# 1_SchDoc.net
KiCad netlist of a schematic drawn in Altium Designer
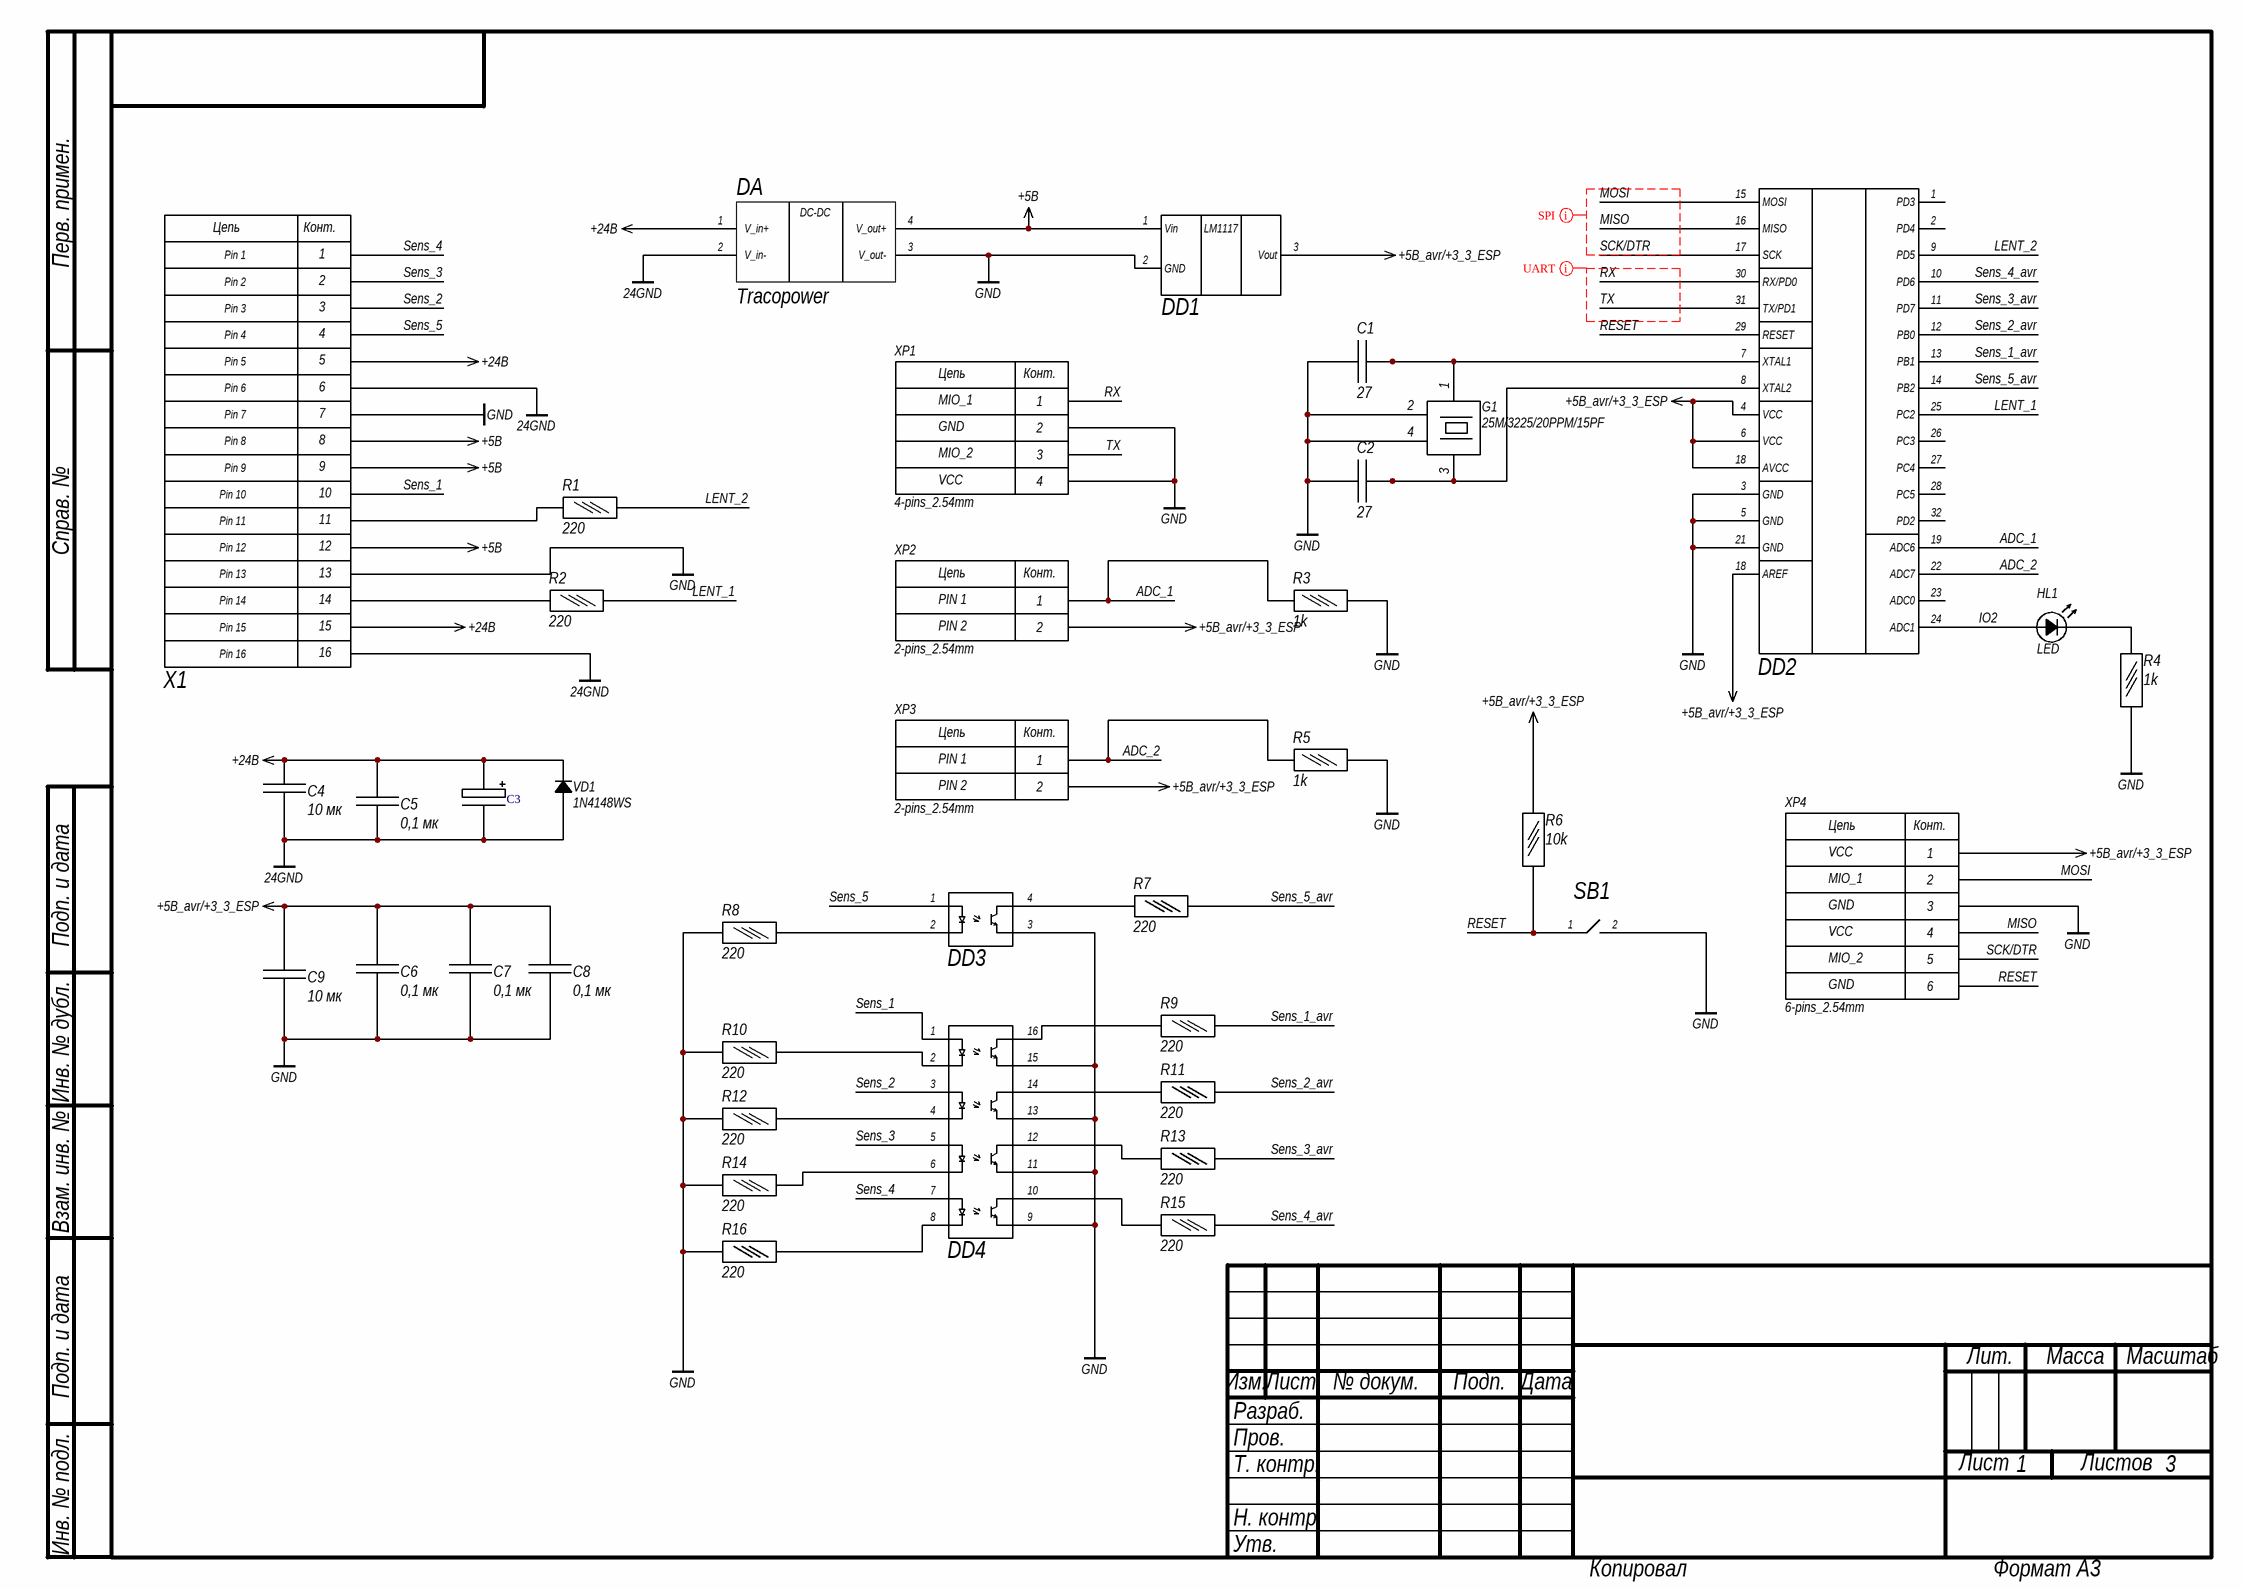
[diagram p0: Лист 1. Основной модуль. SchDoc.SchDoc]

(export (version "E")
  (design (tool "Eeschema 10.0.6"))
  (components
    (comp (ref "C1")
      (value "27")
      (footprint "CAPC1608M")
      (description "0603 X7R 0,1uF 25V 10%")
      (fields
        (field (name "VALUEMANUFACTURERPARTNUMBER") "chip0603 X7R 0,1uF 50V 10%, CC0603KRX7R9BB104, Yageo")
        (field (name "Comment") "CC0603KRX7R8BB104 (0603 X7R 0,1uF 50V 10%)_1")
      )
      (libsource (lib "Конденсаторы") (part "CC0603KRX7R8BB104 (0603 X7R 0,1uF 50V 10%)_1"))
    )
    (comp (ref "C2")
      (value "27")
      (footprint "CAPC1608M")
      (description "0603 X7R 0,1uF 25V 10%")
      (fields
        (field (name "VALUEMANUFACTURERPARTNUMBER") "chip0603 X7R 0,1uF 50V 10%, CC0603KRX7R9BB104, Yageo")
        (field (name "Comment") "CC0603KRX7R8BB104 (0603 X7R 0,1uF 50V 10%)_1")
      )
      (libsource (lib "Конденсаторы") (part "CC0603KRX7R8BB104 (0603 X7R 0,1uF 50V 10%)_1"))
    )
    (comp (ref "C3")
      (value "CAP_SMD_POLAR")
      (footprint "CC_T491C476K016AT")
      (libsource (lib "Cap") (part "CAP_SMD_POLAR"))
    )
    (comp (ref "C4")
      (value "10 мк")
      (footprint "CAPC1608M")
      (description "0603 X7R 0,1uF 25V 10%")
      (fields
        (field (name "VALUEMANUFACTURERPARTNUMBER") "chip0603 X7R 0,1uF 50V 10%, CC0603KRX7R9BB104, Yageo")
        (field (name "Comment") "CC0603KRX7R8BB104 (0603 X7R 0,1uF 50V 10%)_1")
      )
      (libsource (lib "Конденсаторы") (part "CC0603KRX7R8BB104 (0603 X7R 0,1uF 50V 10%)_1"))
    )
    (comp (ref "C5")
      (value "0,1 мк")
      (footprint "CAPC1608M")
      (description "0603 X7R 0,1uF 25V 10%")
      (fields
        (field (name "VALUEMANUFACTURERPARTNUMBER") "chip0603 X7R 0,1uF 50V 10%, CC0603KRX7R9BB104, Yageo")
        (field (name "Comment") "CC0603KRX7R8BB104 (0603 X7R 0,1uF 50V 10%)_1")
      )
      (libsource (lib "Конденсаторы") (part "CC0603KRX7R8BB104 (0603 X7R 0,1uF 50V 10%)_1"))
    )
    (comp (ref "C6")
      (value "0,1 мк")
      (footprint "CAPC1608M")
      (description "0603 X7R 0,1uF 25V 10%")
      (fields
        (field (name "VALUEMANUFACTURERPARTNUMBER") "chip0603 X7R 0,1uF 50V 10%, CC0603KRX7R9BB104, Yageo")
        (field (name "Comment") "CC0603KRX7R8BB104 (0603 X7R 0,1uF 50V 10%)_1")
      )
      (libsource (lib "Конденсаторы") (part "CC0603KRX7R8BB104 (0603 X7R 0,1uF 50V 10%)_1"))
    )
    (comp (ref "C7")
      (value "0,1 мк")
      (footprint "CAPC1608M")
      (description "0603 X7R 0,1uF 25V 10%")
      (fields
        (field (name "VALUEMANUFACTURERPARTNUMBER") "chip0603 X7R 0,1uF 50V 10%, CC0603KRX7R9BB104, Yageo")
        (field (name "Comment") "CC0603KRX7R8BB104 (0603 X7R 0,1uF 50V 10%)_1")
      )
      (libsource (lib "Конденсаторы") (part "CC0603KRX7R8BB104 (0603 X7R 0,1uF 50V 10%)_1"))
    )
    (comp (ref "C8")
      (value "0,1 мк")
      (footprint "CAPC1608M")
      (description "0603 X7R 0,1uF 25V 10%")
      (fields
        (field (name "VALUEMANUFACTURERPARTNUMBER") "chip0603 X7R 0,1uF 50V 10%, CC0603KRX7R9BB104, Yageo")
        (field (name "Comment") "CC0603KRX7R8BB104 (0603 X7R 0,1uF 50V 10%)_1")
      )
      (libsource (lib "Конденсаторы") (part "CC0603KRX7R8BB104 (0603 X7R 0,1uF 50V 10%)_1"))
    )
    (comp (ref "C9")
      (value "10 мк")
      (footprint "CAPC1608M")
      (description "0603 X7R 0,1uF 25V 10%")
      (fields
        (field (name "VALUEMANUFACTURERPARTNUMBER") "chip0603 X7R 0,1uF 50V 10%, CC0603KRX7R9BB104, Yageo")
        (field (name "Comment") "CC0603KRX7R8BB104 (0603 X7R 0,1uF 50V 10%)_1")
      )
      (libsource (lib "Конденсаторы") (part "CC0603KRX7R8BB104 (0603 X7R 0,1uF 50V 10%)_1"))
    )
    (comp (ref "DA")
      (value "Tracopower")
      (footprint "Tracopower")
      (libsource (lib "Microsxeme") (part "TracoPower"))
    )
    (comp (ref "DD1") (value "LM1117") (footprint "SOT-223") (libsource (lib "DC-DC") (part "LM1117")))
    (comp (ref "DD2")
      (value "ATmega328p")
      (footprint "ATmega328P_TQFP")
      (description "32 pins. SPI, UART, 4 CHANNELS ADC, 13 GPIO PORTS")
      (libsource (lib "AVR") (part "ATmega328p"))
    )
    (comp (ref "DD3") (value "IS-281") (footprint "IS-281") (libsource (lib "Opto") (part "IS-281")))
    (comp (ref "DD4") (value "IS-281-4") (footprint "SOIC16") (libsource (lib "Opto") (part "IS-281-4")))
    (comp (ref "G1")
      (value "25M/3225/20PPM/15PF")
      (footprint "EPSON TSX-3225")
      (description "7B025000O01 Резонатор")
      (fields (field (name "VALUEMANUFACTURERPARTNUMBER") "7B25000O01"))
      (libsource (lib "микросхемы") (part "25M/3225/20PPM/15PF"))
    )
    (comp (ref "HL1")
      (value "LED")
      (footprint "LED 0603_1608 BLUE")
      (description "Chip LED")
      (fields (field (name "VALUEMANUFACTURERPARTNUMBER") "Светодиод"))
      (libsource (lib "микросхемы") (part "LED"))
    )
    (comp (ref "R1")
      (value "220")
      (footprint "RESC1608M")
      (description "chip0603 10k 1%")
      (fields
        (field (name "VALUEMANUFACTURERPARTNUMBER") "chip0603 10k 1%, RC0603FR-0710KL, Yageo")
        (field (name "Comment") "RC0603FR-0710KL (0603 10k 1%)")
      )
      (libsource (lib "Резисторы") (part "RC0603FR-0710KL (0603 10k 1%)"))
    )
    (comp (ref "R2")
      (value "220")
      (footprint "RESC1608M")
      (description "chip0603 10k 1%")
      (fields
        (field (name "VALUEMANUFACTURERPARTNUMBER") "chip0603 10k 1%, RC0603FR-0710KL, Yageo")
        (field (name "Comment") "RC0603FR-0710KL (0603 10k 1%)")
      )
      (libsource (lib "Резисторы") (part "RC0603FR-0710KL (0603 10k 1%)"))
    )
    (comp (ref "R3")
      (value "1k")
      (footprint "RESC1608M")
      (description "chip0603 1k 1%")
      (fields
        (field (name "VALUEMANUFACTURERPARTNUMBER") "chip0603 1k 1%, RC0603FR-071KL, Yageo")
        (field (name "Comment") "RC0603FR-071KL (0603 1k 1%)")
      )
      (libsource (lib "Резисторы") (part "RC0603FR-071KL (0603 1k 1%)"))
    )
    (comp (ref "R4")
      (value "1k")
      (footprint "RESC1608M")
      (description "chip0603 1k 1%")
      (fields
        (field (name "VALUEMANUFACTURERPARTNUMBER") "chip0603 1k 1%, RC0603FR-071KL, Yageo")
        (field (name "Comment") "RC0603FR-071KL (0603 1k 1%)")
      )
      (libsource (lib "Резисторы") (part "RC0603FR-071KL (0603 1k 1%)"))
    )
    (comp (ref "R5")
      (value "1k")
      (footprint "RESC1608M")
      (description "chip0603 1k 1%")
      (fields
        (field (name "VALUEMANUFACTURERPARTNUMBER") "chip0603 1k 1%, RC0603FR-071KL, Yageo")
        (field (name "Comment") "RC0603FR-071KL (0603 1k 1%)")
      )
      (libsource (lib "Резисторы") (part "RC0603FR-071KL (0603 1k 1%)"))
    )
    (comp (ref "R6")
      (value "10k")
      (footprint "RESC1608M")
      (description "chip0603 10k 1%")
      (fields
        (field (name "VALUEMANUFACTURERPARTNUMBER") "chip0603 10k 1%, RC0603FR-0710KL, Yageo")
        (field (name "Comment") "RC0603FR-0710KL (0603 10k 1%)")
      )
      (libsource (lib "Резисторы") (part "RC0603FR-0710KL (0603 10k 1%)"))
    )
    (comp (ref "R7")
      (value "220")
      (footprint "RESC1608M")
      (description "chip0603 10k 1%")
      (fields
        (field (name "VALUEMANUFACTURERPARTNUMBER") "chip0603 10k 1%, RC0603FR-0710KL, Yageo")
        (field (name "Comment") "RC0603FR-0710KL (0603 10k 1%)")
      )
      (libsource (lib "Резисторы") (part "RC0603FR-0710KL (0603 10k 1%)"))
    )
    (comp (ref "R8")
      (value "220")
      (footprint "RESC1608M")
      (description "chip0603 10k 1%")
      (fields
        (field (name "VALUEMANUFACTURERPARTNUMBER") "chip0603 10k 1%, RC0603FR-0710KL, Yageo")
        (field (name "Comment") "RC0603FR-0710KL (0603 10k 1%)")
      )
      (libsource (lib "Резисторы") (part "RC0603FR-0710KL (0603 10k 1%)"))
    )
    (comp (ref "R9")
      (value "220")
      (footprint "RESC1608M")
      (description "chip0603 10k 1%")
      (fields
        (field (name "VALUEMANUFACTURERPARTNUMBER") "chip0603 10k 1%, RC0603FR-0710KL, Yageo")
        (field (name "Comment") "RC0603FR-0710KL (0603 10k 1%)")
      )
      (libsource (lib "Резисторы") (part "RC0603FR-0710KL (0603 10k 1%)"))
    )
    (comp (ref "R10")
      (value "220")
      (footprint "RESC1608M")
      (description "chip0603 10k 1%")
      (fields
        (field (name "VALUEMANUFACTURERPARTNUMBER") "chip0603 10k 1%, RC0603FR-0710KL, Yageo")
        (field (name "Comment") "RC0603FR-0710KL (0603 10k 1%)")
      )
      (libsource (lib "Резисторы") (part "RC0603FR-0710KL (0603 10k 1%)"))
    )
    (comp (ref "R11")
      (value "220")
      (footprint "RESC1608M")
      (description "chip0603 10k 1%")
      (fields
        (field (name "VALUEMANUFACTURERPARTNUMBER") "chip0603 10k 1%, RC0603FR-0710KL, Yageo")
        (field (name "Comment") "RC0603FR-0710KL (0603 10k 1%)")
      )
      (libsource (lib "Резисторы") (part "RC0603FR-0710KL (0603 10k 1%)"))
    )
    (comp (ref "R12")
      (value "220")
      (footprint "RESC1608M")
      (description "chip0603 10k 1%")
      (fields
        (field (name "VALUEMANUFACTURERPARTNUMBER") "chip0603 10k 1%, RC0603FR-0710KL, Yageo")
        (field (name "Comment") "RC0603FR-0710KL (0603 10k 1%)")
      )
      (libsource (lib "Резисторы") (part "RC0603FR-0710KL (0603 10k 1%)"))
    )
    (comp (ref "R13")
      (value "220")
      (footprint "RESC1608M")
      (description "chip0603 10k 1%")
      (fields
        (field (name "VALUEMANUFACTURERPARTNUMBER") "chip0603 10k 1%, RC0603FR-0710KL, Yageo")
        (field (name "Comment") "RC0603FR-0710KL (0603 10k 1%)")
      )
      (libsource (lib "Резисторы") (part "RC0603FR-0710KL (0603 10k 1%)"))
    )
    (comp (ref "R14")
      (value "220")
      (footprint "RESC1608M")
      (description "chip0603 10k 1%")
      (fields
        (field (name "VALUEMANUFACTURERPARTNUMBER") "chip0603 10k 1%, RC0603FR-0710KL, Yageo")
        (field (name "Comment") "RC0603FR-0710KL (0603 10k 1%)")
      )
      (libsource (lib "Резисторы") (part "RC0603FR-0710KL (0603 10k 1%)"))
    )
    (comp (ref "R15")
      (value "220")
      (footprint "RESC1608M")
      (description "chip0603 10k 1%")
      (fields
        (field (name "VALUEMANUFACTURERPARTNUMBER") "chip0603 10k 1%, RC0603FR-0710KL, Yageo")
        (field (name "Comment") "RC0603FR-0710KL (0603 10k 1%)")
      )
      (libsource (lib "Резисторы") (part "RC0603FR-0710KL (0603 10k 1%)"))
    )
    (comp (ref "R16")
      (value "220")
      (footprint "RESC1608M")
      (description "chip0603 10k 1%")
      (fields
        (field (name "VALUEMANUFACTURERPARTNUMBER") "chip0603 10k 1%, RC0603FR-0710KL, Yageo")
        (field (name "Comment") "RC0603FR-0710KL (0603 10k 1%)")
      )
      (libsource (lib "Резисторы") (part "RC0603FR-0710KL (0603 10k 1%)"))
    )
    (comp (ref "SB1") (value "Butt") (footprint "B3U1000P") (libsource (lib "buttons") (part "Butt")))
    (comp (ref "VD1")
      (value "1N4148WS")
      (footprint "SOD-323")
      (description "Chip DIOD 100В 150мА")
      (libsource (lib "микросхемы") (part "1N4148WS"))
    )
    (comp (ref "X1")
      (value "348269160")
      (footprint "348269160")
      (libsource (lib "Microsxeme") (part "348269160"))
    )
    (comp (ref "XP1")
      (value "4-pins_2.54mm")
      (footprint "4pins_2.54")
      (fields (field (name "VALUEMANUFACTURERPARTNUMBER") "4 pins"))
      (libsource (lib "микросхемы") (part "4-pins_2.54mm"))
    )
    (comp (ref "XP2")
      (value "2-pins_2.54mm")
      (footprint "2pins_2.54")
      (fields (field (name "VALUEMANUFACTURERPARTNUMBER") "4 pins"))
      (libsource (lib "микросхемы") (part "2-pins_2.54mm"))
    )
    (comp (ref "XP3")
      (value "2-pins_2.54mm")
      (footprint "2pins_2.54")
      (fields (field (name "VALUEMANUFACTURERPARTNUMBER") "4 pins"))
      (libsource (lib "микросхемы") (part "2-pins_2.54mm"))
    )
    (comp (ref "XP4")
      (value "6-pins_2.54mm")
      (footprint "6pins_2.54")
      (fields (field (name "VALUEMANUFACTURERPARTNUMBER") "4 pins"))
      (libsource (lib "микросхемы") (part "6-pins_2.54mm"))
    )
  )
  (nets
    (net (code "1") (name "+5В") (class "Default")
      (node (ref "DA") (pin "4") (pinfunction "V_out+_4") (pintype "open_collector"))
      (node (ref "DD1") (pin "1") (pinfunction "Vin_1") (pintype "open_collector"))
      (node (ref "X1") (pin "12") (pinfunction "Pin_12_12") (pintype "open_collector"))
      (node (ref "X1") (pin "8") (pinfunction "Pin_8_8") (pintype "open_collector"))
      (node (ref "X1") (pin "9") (pinfunction "Pin_9_9") (pintype "open_collector"))
    )
    (net (code "2") (name "+5В_avr{slash}+3_3_ESP") (class "Default")
      (node (ref "C6") (pin "1") (pinfunction "1_1") (pintype "passive"))
      (node (ref "C7") (pin "1") (pinfunction "1_1") (pintype "passive"))
      (node (ref "C8") (pin "1") (pinfunction "1_1") (pintype "passive"))
      (node (ref "C9") (pin "1") (pinfunction "1_1") (pintype "passive"))
      (node (ref "DD1") (pin "3") (pinfunction "Vout_3") (pintype "open_collector"))
      (node (ref "DD2") (pin "18") (pinfunction "AVCC_18") (pintype "passive"))
      (node (ref "DD2") (pin "4") (pinfunction "VCC_4") (pintype "passive"))
      (node (ref "DD2") (pin "6") (pinfunction "VCC_6") (pintype "passive"))
      (node (ref "R6") (pin "2") (pinfunction "2_2") (pintype "passive"))
      (node (ref "XP2") (pin "2") (pinfunction "2_2") (pintype "open_collector"))
      (node (ref "XP3") (pin "2") (pinfunction "2_2") (pintype "open_collector"))
      (node (ref "XP4") (pin "1") (pinfunction "1_1") (pintype "open_collector"))
    )
    (net (code "3") (name "+24В") (class "Default")
      (node (ref "C3") (pin "1") (pinfunction "1_1") (pintype "passive"))
      (node (ref "C4") (pin "1") (pinfunction "1_1") (pintype "passive"))
      (node (ref "C5") (pin "1") (pinfunction "1_1") (pintype "passive"))
      (node (ref "DA") (pin "1") (pinfunction "V_in+_1") (pintype "open_collector"))
      (node (ref "VD1") (pin "2") (pinfunction "-_2") (pintype "passive"))
      (node (ref "X1") (pin "15") (pinfunction "Pin_15_15") (pintype "open_collector"))
      (node (ref "X1") (pin "5") (pinfunction "Pin_5_5") (pintype "open_collector"))
    )
    (net (code "4") (name "/ADC_1") (class "Default")
      (node (ref "DD2") (pin "19") (pinfunction "ADC6_19") (pintype "passive"))
      (node (ref "R3") (pin "2") (pinfunction "2_2") (pintype "passive"))
      (node (ref "XP2") (pin "1") (pinfunction "1_1") (pintype "open_collector"))
    )
    (net (code "5") (name "/ADC_2") (class "Default")
      (node (ref "DD2") (pin "22") (pinfunction "ADC7_22") (pintype "passive"))
      (node (ref "R5") (pin "2") (pinfunction "2_2") (pintype "passive"))
      (node (ref "XP3") (pin "1") (pinfunction "1_1") (pintype "open_collector"))
    )
    (net (code "6") (name "/IO2") (class "Default")
      (node (ref "DD2") (pin "24") (pinfunction "ADC1_24") (pintype "passive"))
      (node (ref "HL1") (pin "1") (pinfunction "A_1") (pintype "passive"))
    )
    (net (code "7") (name "/LENT_1") (class "Default")
      (node (ref "DD2") (pin "25") (pinfunction "PC2_25") (pintype "passive"))
      (node (ref "R2") (pin "2") (pinfunction "2_2") (pintype "passive"))
    )
    (net (code "8") (name "/LENT_2") (class "Default")
      (node (ref "DD2") (pin "9") (pinfunction "PD5_9") (pintype "passive"))
      (node (ref "R1") (pin "2") (pinfunction "2_2") (pintype "passive"))
    )
    (net (code "9") (name "/MISO") (class "Default")
      (node (ref "DD2") (pin "16") (pinfunction "MISO_16") (pintype "passive"))
      (node (ref "XP4") (pin "4") (pinfunction "4_4") (pintype "open_collector"))
    )
    (net (code "10") (name "/MOSI") (class "Default")
      (node (ref "DD2") (pin "15") (pinfunction "MOSI_15") (pintype "passive"))
      (node (ref "XP4") (pin "2") (pinfunction "2_2") (pintype "open_collector"))
    )
    (net (code "11") (name "/RESET") (class "Default")
      (node (ref "DD2") (pin "29") (pinfunction "RESET_29") (pintype "passive"))
      (node (ref "R6") (pin "1") (pinfunction "1_1") (pintype "passive"))
      (node (ref "SB1") (pin "1") (pinfunction "1_1") (pintype "open_collector"))
      (node (ref "XP4") (pin "6") (pinfunction "6_6") (pintype "open_collector"))
    )
    (net (code "12") (name "/RX") (class "Default")
      (node (ref "DD2") (pin "30") (pinfunction "RX/PD0_30") (pintype "passive"))
      (node (ref "XP1") (pin "1") (pinfunction "1_1") (pintype "open_collector"))
    )
    (net (code "13") (name "/SCK{slash}DTR") (class "Default")
      (node (ref "DD2") (pin "17") (pinfunction "SCK_17") (pintype "passive"))
      (node (ref "XP4") (pin "5") (pinfunction "5_5") (pintype "open_collector"))
    )
    (net (code "14") (name "/Sens_1") (class "Default")
      (node (ref "DD4") (pin "1") (pinfunction "1_1") (pintype "open_collector"))
      (node (ref "X1") (pin "10") (pinfunction "Pin_10_10") (pintype "open_collector"))
    )
    (net (code "15") (name "/Sens_1_avr") (class "Default")
      (node (ref "DD2") (pin "13") (pinfunction "PB1_13") (pintype "passive"))
      (node (ref "R9") (pin "2") (pinfunction "2_2") (pintype "passive"))
    )
    (net (code "16") (name "/Sens_2") (class "Default")
      (node (ref "DD4") (pin "3") (pinfunction "3_3") (pintype "open_collector"))
      (node (ref "X1") (pin "3") (pinfunction "Pin_3_3") (pintype "open_collector"))
    )
    (net (code "17") (name "/Sens_2_avr") (class "Default")
      (node (ref "DD2") (pin "12") (pinfunction "PB0_12") (pintype "passive"))
      (node (ref "R11") (pin "2") (pinfunction "2_2") (pintype "passive"))
    )
    (net (code "18") (name "/Sens_3") (class "Default")
      (node (ref "DD4") (pin "5") (pinfunction "5_5") (pintype "open_collector"))
      (node (ref "X1") (pin "2") (pinfunction "Pin_2_2") (pintype "open_collector"))
    )
    (net (code "19") (name "/Sens_3_avr") (class "Default")
      (node (ref "DD2") (pin "11") (pinfunction "PD7_11") (pintype "passive"))
      (node (ref "R13") (pin "2") (pinfunction "2_2") (pintype "passive"))
    )
    (net (code "20") (name "/Sens_4") (class "Default")
      (node (ref "DD4") (pin "7") (pinfunction "7_7") (pintype "open_collector"))
      (node (ref "X1") (pin "1") (pinfunction "Pin_1_1") (pintype "open_collector"))
    )
    (net (code "21") (name "/Sens_4_avr") (class "Default")
      (node (ref "DD2") (pin "10") (pinfunction "PD6_10") (pintype "passive"))
      (node (ref "R15") (pin "2") (pinfunction "2_2") (pintype "passive"))
    )
    (net (code "22") (name "/Sens_5") (class "Default")
      (node (ref "DD3") (pin "1") (pinfunction "1_1") (pintype "open_collector"))
      (node (ref "X1") (pin "4") (pinfunction "Pin_4_4") (pintype "open_collector"))
    )
    (net (code "23") (name "/Sens_5_avr") (class "Default")
      (node (ref "DD2") (pin "14") (pinfunction "PB2_14") (pintype "passive"))
      (node (ref "R7") (pin "2") (pinfunction "2_2") (pintype "passive"))
    )
    (net (code "24") (name "/TX") (class "Default")
      (node (ref "DD2") (pin "31") (pinfunction "TX/PD1_31") (pintype "passive"))
      (node (ref "XP1") (pin "3") (pinfunction "3_3") (pintype "open_collector"))
    )
    (net (code "25") (name "24GND") (class "Default")
      (node (ref "C3") (pin "2") (pinfunction "2_2") (pintype "passive"))
      (node (ref "C4") (pin "2") (pinfunction "2_2") (pintype "passive"))
      (node (ref "C5") (pin "2") (pinfunction "2_2") (pintype "passive"))
      (node (ref "DA") (pin "2") (pinfunction "V_in-_2") (pintype "open_collector"))
      (node (ref "VD1") (pin "1") (pinfunction "+_1") (pintype "passive"))
      (node (ref "X1") (pin "16") (pinfunction "Pin_16_16") (pintype "open_collector"))
      (node (ref "X1") (pin "6") (pinfunction "Pin_6_6") (pintype "open_collector"))
    )
    (net (code "26") (name "GND") (class "Default")
      (node (ref "C1") (pin "1") (pinfunction "1_1") (pintype "passive"))
      (node (ref "C2") (pin "1") (pinfunction "1_1") (pintype "passive"))
      (node (ref "C6") (pin "2") (pinfunction "2_2") (pintype "passive"))
      (node (ref "C7") (pin "2") (pinfunction "2_2") (pintype "passive"))
      (node (ref "C8") (pin "2") (pinfunction "2_2") (pintype "passive"))
      (node (ref "C9") (pin "2") (pinfunction "2_2") (pintype "passive"))
      (node (ref "DA") (pin "3") (pinfunction "V_out-_3") (pintype "open_collector"))
      (node (ref "DD1") (pin "2") (pinfunction "GND_2") (pintype "open_collector"))
      (node (ref "DD2") (pin "21") (pinfunction "GND_21") (pintype "passive"))
      (node (ref "DD2") (pin "3") (pinfunction "GND_3") (pintype "passive"))
      (node (ref "DD2") (pin "5") (pinfunction "GND_5") (pintype "passive"))
      (node (ref "DD3") (pin "3") (pinfunction "3_3") (pintype "open_collector"))
      (node (ref "DD4") (pin "11") (pinfunction "11_11") (pintype "open_collector"))
      (node (ref "DD4") (pin "13") (pinfunction "13_13") (pintype "open_collector"))
      (node (ref "DD4") (pin "15") (pinfunction "15_15") (pintype "open_collector"))
      (node (ref "DD4") (pin "9") (pinfunction "9_9") (pintype "open_collector"))
      (node (ref "G1") (pin "2") (pintype "passive"))
      (node (ref "G1") (pin "4") (pintype "passive"))
      (node (ref "R10") (pin "1") (pinfunction "1_1") (pintype "passive"))
      (node (ref "R12") (pin "1") (pinfunction "1_1") (pintype "passive"))
      (node (ref "R14") (pin "1") (pinfunction "1_1") (pintype "passive"))
      (node (ref "R16") (pin "1") (pinfunction "1_1") (pintype "passive"))
      (node (ref "R3") (pin "1") (pinfunction "1_1") (pintype "passive"))
      (node (ref "R4") (pin "1") (pinfunction "1_1") (pintype "passive"))
      (node (ref "R5") (pin "1") (pinfunction "1_1") (pintype "passive"))
      (node (ref "R8") (pin "1") (pinfunction "1_1") (pintype "passive"))
      (node (ref "SB1") (pin "2") (pinfunction "2_2") (pintype "open_collector"))
      (node (ref "X1") (pin "13") (pinfunction "Pin_13_13") (pintype "open_collector"))
      (node (ref "X1") (pin "7") (pinfunction "Pin_7_7") (pintype "open_collector"))
      (node (ref "XP1") (pin "2") (pinfunction "2_2") (pintype "open_collector"))
      (node (ref "XP1") (pin "4") (pinfunction "4_4") (pintype "open_collector"))
      (node (ref "XP4") (pin "3") (pinfunction "3_3") (pintype "open_collector"))
    )
    (net (code "27") (name "Net-(DD2-XTAL1)") (class "Default")
      (node (ref "C1") (pin "2") (pinfunction "2_2") (pintype "passive"))
      (node (ref "DD2") (pin "7") (pinfunction "XTAL1_7") (pintype "passive"))
      (node (ref "G1") (pin "1") (pinfunction "A_1") (pintype "passive"))
    )
    (net (code "28") (name "Net-(DD2-XTAL2)") (class "Default")
      (node (ref "C2") (pin "2") (pinfunction "2_2") (pintype "passive"))
      (node (ref "DD2") (pin "8") (pinfunction "XTAL2_8") (pintype "passive"))
      (node (ref "G1") (pin "3") (pintype "passive"))
    )
    (net (code "29") (name "Net-(DD3-Pad2)") (class "Default")
      (node (ref "DD3") (pin "2") (pinfunction "2_2") (pintype "open_collector"))
      (node (ref "R8") (pin "2") (pinfunction "2_2") (pintype "passive"))
    )
    (net (code "30") (name "Net-(DD3-Pad4)") (class "Default")
      (node (ref "DD3") (pin "4") (pinfunction "4_4") (pintype "open_collector"))
      (node (ref "R7") (pin "1") (pinfunction "1_1") (pintype "passive"))
    )
    (net (code "31") (name "Net-(DD4-Pad2)") (class "Default")
      (node (ref "DD4") (pin "2") (pinfunction "2_2") (pintype "open_collector"))
      (node (ref "R10") (pin "2") (pinfunction "2_2") (pintype "passive"))
    )
    (net (code "32") (name "Net-(DD4-Pad4)") (class "Default")
      (node (ref "DD4") (pin "4") (pinfunction "4_4") (pintype "open_collector"))
      (node (ref "R12") (pin "2") (pinfunction "2_2") (pintype "passive"))
    )
    (net (code "33") (name "Net-(DD4-Pad6)") (class "Default")
      (node (ref "DD4") (pin "6") (pinfunction "6_6") (pintype "open_collector"))
      (node (ref "R14") (pin "2") (pinfunction "2_2") (pintype "passive"))
    )
    (net (code "34") (name "Net-(DD4-Pad8)") (class "Default")
      (node (ref "DD4") (pin "8") (pinfunction "8_8") (pintype "open_collector"))
      (node (ref "R16") (pin "2") (pinfunction "2_2") (pintype "passive"))
    )
    (net (code "35") (name "Net-(DD4-Pad10)") (class "Default")
      (node (ref "DD4") (pin "10") (pinfunction "10_10") (pintype "open_collector"))
      (node (ref "R15") (pin "1") (pinfunction "1_1") (pintype "passive"))
    )
    (net (code "36") (name "Net-(DD4-Pad12)") (class "Default")
      (node (ref "DD4") (pin "12") (pinfunction "12_12") (pintype "open_collector"))
      (node (ref "R13") (pin "1") (pinfunction "1_1") (pintype "passive"))
    )
    (net (code "37") (name "Net-(DD4-Pad14)") (class "Default")
      (node (ref "DD4") (pin "14") (pinfunction "14_14") (pintype "open_collector"))
      (node (ref "R11") (pin "1") (pinfunction "1_1") (pintype "passive"))
    )
    (net (code "38") (name "Net-(DD4-Pad16)") (class "Default")
      (node (ref "DD4") (pin "16") (pinfunction "16_16") (pintype "open_collector"))
      (node (ref "R9") (pin "1") (pinfunction "1_1") (pintype "passive"))
    )
    (net (code "39") (name "Net-(HL1-C)") (class "Default")
      (node (ref "HL1") (pin "2") (pinfunction "C_2") (pintype "passive"))
      (node (ref "R4") (pin "2") (pinfunction "2_2") (pintype "passive"))
    )
    (net (code "40") (name "Net-(X1-Pin_11)") (class "Default")
      (node (ref "R1") (pin "1") (pinfunction "1_1") (pintype "passive"))
      (node (ref "X1") (pin "11") (pinfunction "Pin_11_11") (pintype "open_collector"))
    )
    (net (code "41") (name "Net-(X1-Pin_14)") (class "Default")
      (node (ref "R2") (pin "1") (pinfunction "1_1") (pintype "passive"))
      (node (ref "X1") (pin "14") (pinfunction "Pin_14_14") (pintype "open_collector"))
    )
    (net (code "42") (name "unconnected-(DA-Pad5)") (class "Default")
      (node (ref "DA") (pin "5") (pinfunction "5_5") (pintype "open_collector"))
    )
    (net (code "43") (name "unconnected-(DD2-ADC0-Pad23)") (class "Default")
      (node (ref "DD2") (pin "23") (pinfunction "ADC0_23") (pintype "passive"))
    )
    (net (code "44") (name "unconnected-(DD2-PC3-Pad26)") (class "Default")
      (node (ref "DD2") (pin "26") (pinfunction "PC3_26") (pintype "passive"))
    )
    (net (code "45") (name "unconnected-(DD2-PC4-Pad27)") (class "Default")
      (node (ref "DD2") (pin "27") (pinfunction "PC4_27") (pintype "passive"))
    )
    (net (code "46") (name "unconnected-(DD2-PC5-Pad28)") (class "Default")
      (node (ref "DD2") (pin "28") (pinfunction "PC5_28") (pintype "passive"))
    )
    (net (code "47") (name "unconnected-(DD2-PD2-Pad32)") (class "Default")
      (node (ref "DD2") (pin "32") (pinfunction "PD2_32") (pintype "passive"))
    )
    (net (code "48") (name "unconnected-(DD2-PD3-Pad1)") (class "Default")
      (node (ref "DD2") (pin "1") (pinfunction "PD3_1") (pintype "passive"))
    )
    (net (code "49") (name "unconnected-(DD2-PD4-Pad2)") (class "Default")
      (node (ref "DD2") (pin "2") (pinfunction "PD4_2") (pintype "passive"))
    )
  )
)
